# motor_driver_ver3_2.net
KiCad netlist of a schematic drawn in EAGLE
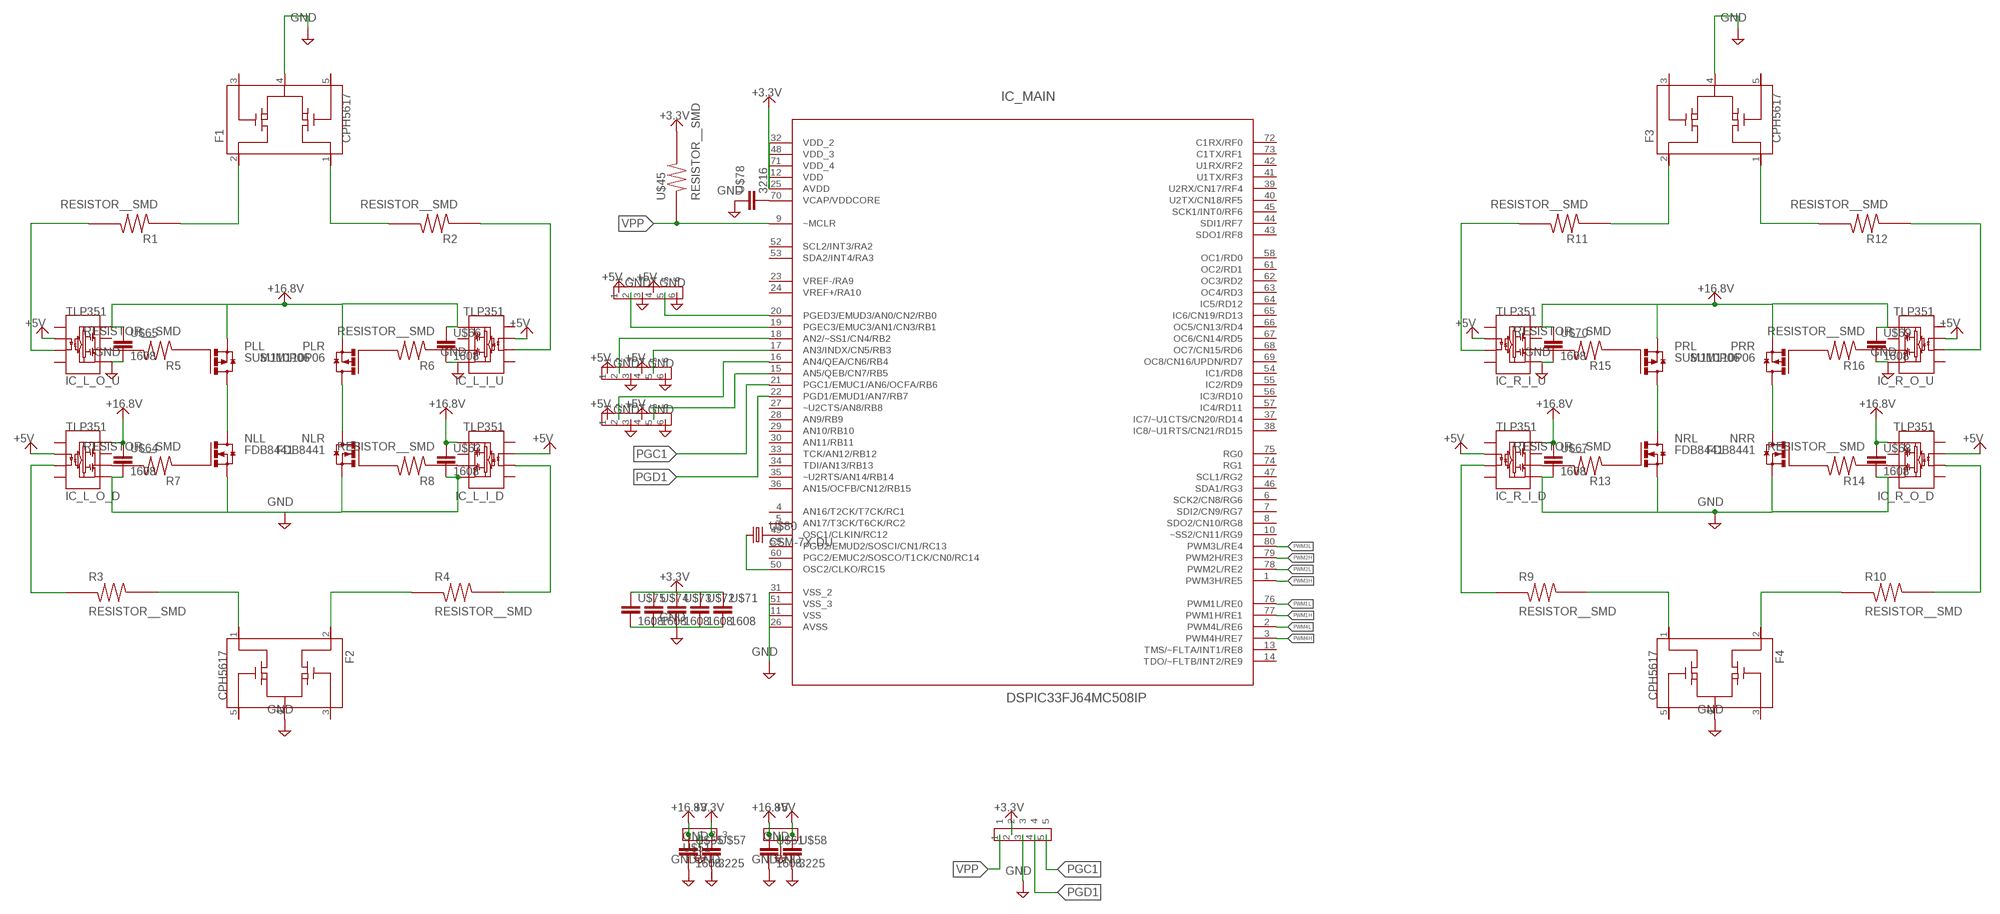
[diagram p0: schematic, sheet 1]

(export (version "E")
  (design (tool "Eeschema 10.0.6"))
  (components
    (comp (ref "F1")
      (value "CPH5617")
      (footprint "eagle-import:CHP-5")
      (libsource (lib "eagle-import") (part "CPH5617"))
    )
    (comp (ref "F2")
      (value "CPH5617")
      (footprint "eagle-import:CHP-5")
      (libsource (lib "eagle-import") (part "CPH5617"))
    )
    (comp (ref "F3")
      (value "CPH5617")
      (footprint "eagle-import:CHP-5")
      (libsource (lib "eagle-import") (part "CPH5617"))
    )
    (comp (ref "F4")
      (value "CPH5617")
      (footprint "eagle-import:CHP-5")
      (libsource (lib "eagle-import") (part "CPH5617"))
    )
    (comp (ref "IC_L_I_D")
      (value "TLP351")
      (footprint "eagle-import:DIL08")
      (libsource (lib "eagle-import") (part "TLP351"))
    )
    (comp (ref "IC_L_I_U")
      (value "TLP351")
      (footprint "eagle-import:DIL08")
      (libsource (lib "eagle-import") (part "TLP351"))
    )
    (comp (ref "IC_L_O_D")
      (value "TLP351")
      (footprint "eagle-import:DIL08")
      (libsource (lib "eagle-import") (part "TLP351"))
    )
    (comp (ref "IC_L_O_U")
      (value "TLP351")
      (footprint "eagle-import:DIL08")
      (libsource (lib "eagle-import") (part "TLP351"))
    )
    (comp (ref "IC_MAIN")
      (value "DSPIC33FJ64MC508IP")
      (footprint "eagle-import:QFP50P1400X1400X120-80N")
      (libsource (lib "eagle-import") (part "DSPIC33FJ64MC508IP"))
    )
    (comp (ref "IC_R_I_D")
      (value "TLP351")
      (footprint "eagle-import:DIL08")
      (libsource (lib "eagle-import") (part "TLP351"))
    )
    (comp (ref "IC_R_I_U")
      (value "TLP351")
      (footprint "eagle-import:DIL08")
      (libsource (lib "eagle-import") (part "TLP351"))
    )
    (comp (ref "IC_R_O_D")
      (value "TLP351")
      (footprint "eagle-import:DIL08")
      (libsource (lib "eagle-import") (part "TLP351"))
    )
    (comp (ref "IC_R_O_U")
      (value "TLP351")
      (footprint "eagle-import:DIL08")
      (libsource (lib "eagle-import") (part "TLP351"))
    )
    (comp (ref "NLL")
      (value "FDB8441")
      (footprint "eagle-import:TO-263")
      (libsource (lib "eagle-import") (part "FDB8441"))
    )
    (comp (ref "NLR")
      (value "FDB8441")
      (footprint "eagle-import:TO-263")
      (libsource (lib "eagle-import") (part "FDB8441"))
    )
    (comp (ref "NRL")
      (value "FDB8441")
      (footprint "eagle-import:TO-263")
      (libsource (lib "eagle-import") (part "FDB8441"))
    )
    (comp (ref "NRR")
      (value "FDB8441")
      (footprint "eagle-import:TO-263")
      (libsource (lib "eagle-import") (part "FDB8441"))
    )
    (comp (ref "PLL")
      (value "SUM110P06")
      (footprint "eagle-import:TO-263")
      (libsource (lib "eagle-import") (part "SUM110P06"))
    )
    (comp (ref "PLR")
      (value "SUM110P06")
      (footprint "eagle-import:TO-263")
      (libsource (lib "eagle-import") (part "SUM110P06"))
    )
    (comp (ref "PRL")
      (value "SUM110P06")
      (footprint "eagle-import:TO-263")
      (libsource (lib "eagle-import") (part "SUM110P06"))
    )
    (comp (ref "PRR")
      (value "SUM110P06")
      (footprint "eagle-import:TO-263")
      (libsource (lib "eagle-import") (part "SUM110P06"))
    )
    (comp (ref "R1")
      (value "RESISTOR__SMD")
      (footprint "eagle-import:1608")
      (libsource (lib "eagle-import") (part "RESISTOR__SMD"))
    )
    (comp (ref "R2")
      (value "RESISTOR__SMD")
      (footprint "eagle-import:1608")
      (libsource (lib "eagle-import") (part "RESISTOR__SMD"))
    )
    (comp (ref "R3")
      (value "RESISTOR__SMD")
      (footprint "eagle-import:1608")
      (libsource (lib "eagle-import") (part "RESISTOR__SMD"))
    )
    (comp (ref "R4")
      (value "RESISTOR__SMD")
      (footprint "eagle-import:1608")
      (libsource (lib "eagle-import") (part "RESISTOR__SMD"))
    )
    (comp (ref "R5")
      (value "RESISTOR__SMD")
      (footprint "eagle-import:1608")
      (libsource (lib "eagle-import") (part "RESISTOR__SMD"))
    )
    (comp (ref "R6")
      (value "RESISTOR__SMD")
      (footprint "eagle-import:1608")
      (libsource (lib "eagle-import") (part "RESISTOR__SMD"))
    )
    (comp (ref "R7")
      (value "RESISTOR__SMD")
      (footprint "eagle-import:1608")
      (libsource (lib "eagle-import") (part "RESISTOR__SMD"))
    )
    (comp (ref "R8")
      (value "RESISTOR__SMD")
      (footprint "eagle-import:1608")
      (libsource (lib "eagle-import") (part "RESISTOR__SMD"))
    )
    (comp (ref "R9")
      (value "RESISTOR__SMD")
      (footprint "eagle-import:1608")
      (libsource (lib "eagle-import") (part "RESISTOR__SMD"))
    )
    (comp (ref "R10")
      (value "RESISTOR__SMD")
      (footprint "eagle-import:1608")
      (libsource (lib "eagle-import") (part "RESISTOR__SMD"))
    )
    (comp (ref "R11")
      (value "RESISTOR__SMD")
      (footprint "eagle-import:1608")
      (libsource (lib "eagle-import") (part "RESISTOR__SMD"))
    )
    (comp (ref "R12")
      (value "RESISTOR__SMD")
      (footprint "eagle-import:1608")
      (libsource (lib "eagle-import") (part "RESISTOR__SMD"))
    )
    (comp (ref "R13")
      (value "RESISTOR__SMD")
      (footprint "eagle-import:1608")
      (libsource (lib "eagle-import") (part "RESISTOR__SMD"))
    )
    (comp (ref "R14")
      (value "RESISTOR__SMD")
      (footprint "eagle-import:1608")
      (libsource (lib "eagle-import") (part "RESISTOR__SMD"))
    )
    (comp (ref "R15")
      (value "RESISTOR__SMD")
      (footprint "eagle-import:1608")
      (libsource (lib "eagle-import") (part "RESISTOR__SMD"))
    )
    (comp (ref "R16")
      (value "RESISTOR__SMD")
      (footprint "eagle-import:1608")
      (libsource (lib "eagle-import") (part "RESISTOR__SMD"))
    )
    (comp (ref "U$1")
      (value "PIN_HEADER_5")
      (footprint "eagle-import:PIN_HEADER_5")
      (libsource (lib "eagle-import") (part "PIN_HEADER_5"))
    )
    (comp (ref "U$4")
      (value "PIN_HEADER_6")
      (footprint "eagle-import:PIN_HEADER_6")
      (libsource (lib "eagle-import") (part "PIN_HEADER_6"))
    )
    (comp (ref "U$5")
      (value "PIN_HEADER_6")
      (footprint "eagle-import:PIN_HEADER_6")
      (libsource (lib "eagle-import") (part "PIN_HEADER_6"))
    )
    (comp (ref "U$20")
      (value "PIN_HEADER_6")
      (footprint "eagle-import:PIN_HEADER_6")
      (libsource (lib "eagle-import") (part "PIN_HEADER_6"))
    )
    (comp (ref "U$45")
      (value "RESISTOR__SMD")
      (footprint "eagle-import:1608")
      (libsource (lib "eagle-import") (part "RESISTOR__SMD"))
    )
    (comp (ref "U$47")
      (value "TA48M05")
      (footprint "eagle-import:ＨＳＩＰ３")
      (libsource (lib "eagle-import") (part "TA48M05"))
    )
    (comp (ref "U$51")
      (value "TA48M033")
      (footprint "eagle-import:ＨＳＩＰ３")
      (libsource (lib "eagle-import") (part "TA48M033"))
    )
    (comp (ref "U$55")
      (value "1608")
      (footprint "eagle-import:1608")
      (libsource (lib "eagle-import") (part "1608"))
    )
    (comp (ref "U$57")
      (value "3225")
      (footprint "eagle-import:3225")
      (libsource (lib "eagle-import") (part "3225"))
    )
    (comp (ref "U$58")
      (value "3225")
      (footprint "eagle-import:3225")
      (libsource (lib "eagle-import") (part "3225"))
    )
    (comp (ref "U$61")
      (value "1608")
      (footprint "eagle-import:1608")
      (libsource (lib "eagle-import") (part "1608"))
    )
    (comp (ref "U$63")
      (value "1608")
      (footprint "eagle-import:1608")
      (libsource (lib "eagle-import") (part "1608"))
    )
    (comp (ref "U$64")
      (value "1608")
      (footprint "eagle-import:1608")
      (libsource (lib "eagle-import") (part "1608"))
    )
    (comp (ref "U$65")
      (value "1608")
      (footprint "eagle-import:1608")
      (libsource (lib "eagle-import") (part "1608"))
    )
    (comp (ref "U$66")
      (value "1608")
      (footprint "eagle-import:1608")
      (libsource (lib "eagle-import") (part "1608"))
    )
    (comp (ref "U$67")
      (value "1608")
      (footprint "eagle-import:1608")
      (libsource (lib "eagle-import") (part "1608"))
    )
    (comp (ref "U$68")
      (value "1608")
      (footprint "eagle-import:1608")
      (libsource (lib "eagle-import") (part "1608"))
    )
    (comp (ref "U$69")
      (value "1608")
      (footprint "eagle-import:1608")
      (libsource (lib "eagle-import") (part "1608"))
    )
    (comp (ref "U$70")
      (value "1608")
      (footprint "eagle-import:1608")
      (libsource (lib "eagle-import") (part "1608"))
    )
    (comp (ref "U$71")
      (value "1608")
      (footprint "eagle-import:1608")
      (libsource (lib "eagle-import") (part "1608"))
    )
    (comp (ref "U$72")
      (value "1608")
      (footprint "eagle-import:1608")
      (libsource (lib "eagle-import") (part "1608"))
    )
    (comp (ref "U$73")
      (value "1608")
      (footprint "eagle-import:1608")
      (libsource (lib "eagle-import") (part "1608"))
    )
    (comp (ref "U$74")
      (value "1608")
      (footprint "eagle-import:1608")
      (libsource (lib "eagle-import") (part "1608"))
    )
    (comp (ref "U$75")
      (value "1608")
      (footprint "eagle-import:1608")
      (libsource (lib "eagle-import") (part "1608"))
    )
    (comp (ref "U$78")
      (value "3216")
      (footprint "eagle-import:3216")
      (libsource (lib "eagle-import") (part "3216"))
    )
    (comp (ref "U$80")
      (value "CSM-7X-DU")
      (footprint "eagle-import:CSM-7X-DU")
      (libsource (lib "eagle-import") (part "CSM-7X-DU"))
    )
  )
  (nets
    (net (code "1") (name "+3.3V") (class "Default")
      (node (ref "IC_MAIN") (pin "12") (pinfunction "VDD_12") (pintype "power_in"))
      (node (ref "IC_MAIN") (pin "25") (pinfunction "AVDD_25") (pintype "power_in"))
      (node (ref "IC_MAIN") (pin "32") (pinfunction "VDD_2_32") (pintype "power_in"))
      (node (ref "IC_MAIN") (pin "48") (pinfunction "VDD_3_48") (pintype "power_in"))
      (node (ref "IC_MAIN") (pin "71") (pinfunction "VDD_4_71") (pintype "power_in"))
      (node (ref "U$1") (pin "2") (pinfunction "2_2") (pintype "bidirectional"))
      (node (ref "U$45") (pin "2") (pinfunction "P$2_2") (pintype "passive"))
      (node (ref "U$51") (pin "3") (pinfunction "3_3") (pintype "bidirectional"))
      (node (ref "U$57") (pin "P$1") (pinfunction "1_P$1") (pintype "passive"))
      (node (ref "U$71") (pin "P$1") (pinfunction "1_P$1") (pintype "passive"))
      (node (ref "U$72") (pin "P$1") (pinfunction "1_P$1") (pintype "passive"))
      (node (ref "U$73") (pin "P$1") (pinfunction "1_P$1") (pintype "passive"))
      (node (ref "U$74") (pin "P$1") (pinfunction "1_P$1") (pintype "passive"))
      (node (ref "U$75") (pin "P$1") (pinfunction "1_P$1") (pintype "passive"))
    )
    (net (code "2") (name "+5V") (class "Default")
      (node (ref "IC_L_I_D") (pin "2") (pinfunction "LED+_2") (pintype "bidirectional"))
      (node (ref "IC_L_I_U") (pin "2") (pinfunction "LED+_2") (pintype "bidirectional"))
      (node (ref "IC_L_O_D") (pin "2") (pinfunction "LED+_2") (pintype "bidirectional"))
      (node (ref "IC_L_O_U") (pin "2") (pinfunction "LED+_2") (pintype "bidirectional"))
      (node (ref "IC_R_I_D") (pin "2") (pinfunction "LED+_2") (pintype "bidirectional"))
      (node (ref "IC_R_I_U") (pin "2") (pinfunction "LED+_2") (pintype "bidirectional"))
      (node (ref "IC_R_O_D") (pin "2") (pinfunction "LED+_2") (pintype "bidirectional"))
      (node (ref "IC_R_O_U") (pin "2") (pinfunction "LED+_2") (pintype "bidirectional"))
      (node (ref "U$20") (pin "1") (pinfunction "1_1") (pintype "bidirectional"))
      (node (ref "U$20") (pin "4") (pinfunction "4_4") (pintype "bidirectional"))
      (node (ref "U$4") (pin "1") (pinfunction "1_1") (pintype "bidirectional"))
      (node (ref "U$4") (pin "4") (pinfunction "4_4") (pintype "bidirectional"))
      (node (ref "U$47") (pin "3") (pinfunction "OUT_3") (pintype "bidirectional"))
      (node (ref "U$5") (pin "1") (pinfunction "1_1") (pintype "bidirectional"))
      (node (ref "U$5") (pin "4") (pinfunction "4_4") (pintype "bidirectional"))
      (node (ref "U$58") (pin "P$1") (pinfunction "1_P$1") (pintype "passive"))
    )
    (net (code "3") (name "+16.8V") (class "Default")
      (node (ref "IC_L_I_D") (pin "8") (pinfunction "VDD_8") (pintype "bidirectional"))
      (node (ref "IC_L_I_U") (pin "8") (pinfunction "VDD_8") (pintype "bidirectional"))
      (node (ref "IC_L_O_D") (pin "8") (pinfunction "VDD_8") (pintype "bidirectional"))
      (node (ref "IC_L_O_U") (pin "8") (pinfunction "VDD_8") (pintype "bidirectional"))
      (node (ref "IC_R_I_D") (pin "8") (pinfunction "VDD_8") (pintype "bidirectional"))
      (node (ref "IC_R_I_U") (pin "8") (pinfunction "VDD_8") (pintype "bidirectional"))
      (node (ref "IC_R_O_D") (pin "8") (pinfunction "VDD_8") (pintype "bidirectional"))
      (node (ref "IC_R_O_U") (pin "8") (pinfunction "VDD_8") (pintype "bidirectional"))
      (node (ref "PLL") (pin "2") (pinfunction "S_2") (pintype "passive"))
      (node (ref "PLR") (pin "2") (pinfunction "S_2") (pintype "passive"))
      (node (ref "PRL") (pin "2") (pinfunction "S_2") (pintype "passive"))
      (node (ref "PRR") (pin "2") (pinfunction "S_2") (pintype "passive"))
      (node (ref "U$47") (pin "1") (pinfunction "IN_1") (pintype "bidirectional"))
      (node (ref "U$51") (pin "1") (pinfunction "1_1") (pintype "bidirectional"))
      (node (ref "U$55") (pin "P$1") (pinfunction "1_P$1") (pintype "passive"))
      (node (ref "U$61") (pin "P$1") (pinfunction "1_P$1") (pintype "passive"))
      (node (ref "U$63") (pin "P$1") (pinfunction "1_P$1") (pintype "passive"))
      (node (ref "U$64") (pin "P$1") (pinfunction "1_P$1") (pintype "passive"))
      (node (ref "U$65") (pin "P$1") (pinfunction "1_P$1") (pintype "passive"))
      (node (ref "U$66") (pin "P$1") (pinfunction "1_P$1") (pintype "passive"))
      (node (ref "U$67") (pin "P$1") (pinfunction "1_P$1") (pintype "passive"))
      (node (ref "U$68") (pin "P$1") (pinfunction "1_P$1") (pintype "passive"))
      (node (ref "U$69") (pin "P$1") (pinfunction "1_P$1") (pintype "passive"))
      (node (ref "U$70") (pin "P$1") (pinfunction "1_P$1") (pintype "passive"))
    )
    (net (code "4") (name "GND") (class "Default")
      (node (ref "F1") (pin "4") (pinfunction "S_4") (pintype "bidirectional"))
      (node (ref "F2") (pin "4") (pinfunction "S_4") (pintype "bidirectional"))
      (node (ref "F3") (pin "4") (pinfunction "S_4") (pintype "bidirectional"))
      (node (ref "F4") (pin "4") (pinfunction "S_4") (pintype "bidirectional"))
      (node (ref "IC_L_I_D") (pin "5") (pinfunction "GND_5") (pintype "bidirectional"))
      (node (ref "IC_L_I_U") (pin "5") (pinfunction "GND_5") (pintype "bidirectional"))
      (node (ref "IC_L_O_D") (pin "5") (pinfunction "GND_5") (pintype "bidirectional"))
      (node (ref "IC_L_O_U") (pin "5") (pinfunction "GND_5") (pintype "bidirectional"))
      (node (ref "IC_MAIN") (pin "11") (pinfunction "VSS_11") (pintype "power_in"))
      (node (ref "IC_MAIN") (pin "26") (pinfunction "AVSS_26") (pintype "power_in"))
      (node (ref "IC_MAIN") (pin "31") (pinfunction "VSS_2_31") (pintype "power_in"))
      (node (ref "IC_MAIN") (pin "51") (pinfunction "VSS_3_51") (pintype "power_in"))
      (node (ref "IC_R_I_D") (pin "5") (pinfunction "GND_5") (pintype "bidirectional"))
      (node (ref "IC_R_I_U") (pin "5") (pinfunction "GND_5") (pintype "bidirectional"))
      (node (ref "IC_R_O_D") (pin "5") (pinfunction "GND_5") (pintype "bidirectional"))
      (node (ref "IC_R_O_U") (pin "5") (pinfunction "GND_5") (pintype "bidirectional"))
      (node (ref "NLL") (pin "2") (pinfunction "S_2") (pintype "passive"))
      (node (ref "NLR") (pin "2") (pinfunction "S_2") (pintype "passive"))
      (node (ref "NRL") (pin "2") (pinfunction "S_2") (pintype "passive"))
      (node (ref "NRR") (pin "2") (pinfunction "S_2") (pintype "passive"))
      (node (ref "U$1") (pin "3") (pinfunction "3_3") (pintype "bidirectional"))
      (node (ref "U$20") (pin "3") (pinfunction "3_3") (pintype "bidirectional"))
      (node (ref "U$20") (pin "6") (pinfunction "6_6") (pintype "bidirectional"))
      (node (ref "U$4") (pin "3") (pinfunction "3_3") (pintype "bidirectional"))
      (node (ref "U$4") (pin "6") (pinfunction "6_6") (pintype "bidirectional"))
      (node (ref "U$47") (pin "2") (pinfunction "GND_2") (pintype "bidirectional"))
      (node (ref "U$5") (pin "3") (pinfunction "3_3") (pintype "bidirectional"))
      (node (ref "U$5") (pin "6") (pinfunction "6_6") (pintype "bidirectional"))
      (node (ref "U$51") (pin "2") (pinfunction "2_2") (pintype "bidirectional"))
      (node (ref "U$55") (pin "P$2") (pinfunction "2_P$2") (pintype "passive"))
      (node (ref "U$57") (pin "P$2") (pinfunction "2_P$2") (pintype "passive"))
      (node (ref "U$58") (pin "P$2") (pinfunction "2_P$2") (pintype "passive"))
      (node (ref "U$61") (pin "P$2") (pinfunction "2_P$2") (pintype "passive"))
      (node (ref "U$63") (pin "P$2") (pinfunction "2_P$2") (pintype "passive"))
      (node (ref "U$64") (pin "P$2") (pinfunction "2_P$2") (pintype "passive"))
      (node (ref "U$65") (pin "P$2") (pinfunction "2_P$2") (pintype "passive"))
      (node (ref "U$66") (pin "P$2") (pinfunction "2_P$2") (pintype "passive"))
      (node (ref "U$67") (pin "P$2") (pinfunction "2_P$2") (pintype "passive"))
      (node (ref "U$68") (pin "P$2") (pinfunction "2_P$2") (pintype "passive"))
      (node (ref "U$69") (pin "P$2") (pinfunction "2_P$2") (pintype "passive"))
      (node (ref "U$70") (pin "P$2") (pinfunction "2_P$2") (pintype "passive"))
      (node (ref "U$71") (pin "P$2") (pinfunction "2_P$2") (pintype "passive"))
      (node (ref "U$72") (pin "P$2") (pinfunction "2_P$2") (pintype "passive"))
      (node (ref "U$73") (pin "P$2") (pinfunction "2_P$2") (pintype "passive"))
      (node (ref "U$74") (pin "P$2") (pinfunction "2_P$2") (pintype "passive"))
      (node (ref "U$75") (pin "P$2") (pinfunction "2_P$2") (pintype "passive"))
      (node (ref "U$78") (pin "P$1") (pinfunction "1_P$1") (pintype "passive"))
    )
    (net (code "5") (name "Net-(F1-D1)") (class "Default")
      (node (ref "F1") (pin "1") (pinfunction "D1_1") (pintype "bidirectional"))
      (node (ref "R2") (pin "2") (pinfunction "P$2_2") (pintype "passive"))
    )
    (net (code "6") (name "Net-(F1-D2)") (class "Default")
      (node (ref "F1") (pin "2") (pinfunction "D2_2") (pintype "bidirectional"))
      (node (ref "R1") (pin "1") (pinfunction "P$1_1") (pintype "passive"))
    )
    (net (code "7") (name "Net-(F2-D1)") (class "Default")
      (node (ref "F2") (pin "1") (pinfunction "D1_1") (pintype "bidirectional"))
      (node (ref "R3") (pin "2") (pinfunction "P$2_2") (pintype "passive"))
    )
    (net (code "8") (name "Net-(F2-D2)") (class "Default")
      (node (ref "F2") (pin "2") (pinfunction "D2_2") (pintype "bidirectional"))
      (node (ref "R4") (pin "1") (pinfunction "P$1_1") (pintype "passive"))
    )
    (net (code "9") (name "Net-(F3-D1)") (class "Default")
      (node (ref "F3") (pin "1") (pinfunction "D1_1") (pintype "bidirectional"))
      (node (ref "R12") (pin "2") (pinfunction "P$2_2") (pintype "passive"))
    )
    (net (code "10") (name "Net-(F3-D2)") (class "Default")
      (node (ref "F3") (pin "2") (pinfunction "D2_2") (pintype "bidirectional"))
      (node (ref "R11") (pin "1") (pinfunction "P$1_1") (pintype "passive"))
    )
    (net (code "11") (name "Net-(F4-D1)") (class "Default")
      (node (ref "F4") (pin "1") (pinfunction "D1_1") (pintype "bidirectional"))
      (node (ref "R9") (pin "2") (pinfunction "P$2_2") (pintype "passive"))
    )
    (net (code "12") (name "Net-(F4-D2)") (class "Default")
      (node (ref "F4") (pin "2") (pinfunction "D2_2") (pintype "bidirectional"))
      (node (ref "R10") (pin "1") (pinfunction "P$1_1") (pintype "passive"))
    )
    (net (code "13") (name "Net-(IC_L_I_D-LED-)") (class "Default")
      (node (ref "IC_L_I_D") (pin "3") (pinfunction "LED-_3") (pintype "bidirectional"))
      (node (ref "R4") (pin "2") (pinfunction "P$2_2") (pintype "passive"))
    )
    (net (code "14") (name "Net-(IC_L_I_D-OUT)") (class "Default")
      (node (ref "IC_L_I_D") (pin "6") (pinfunction "OUT_6") (pintype "output"))
      (node (ref "R8") (pin "1") (pinfunction "P$1_1") (pintype "passive"))
    )
    (net (code "15") (name "Net-(IC_L_I_U-LED-)") (class "Default")
      (node (ref "IC_L_I_U") (pin "3") (pinfunction "LED-_3") (pintype "bidirectional"))
      (node (ref "R2") (pin "1") (pinfunction "P$1_1") (pintype "passive"))
    )
    (net (code "16") (name "Net-(IC_L_I_U-OUT)") (class "Default")
      (node (ref "IC_L_I_U") (pin "6") (pinfunction "OUT_6") (pintype "output"))
      (node (ref "R6") (pin "1") (pinfunction "P$1_1") (pintype "passive"))
    )
    (net (code "17") (name "Net-(IC_L_O_D-LED-)") (class "Default")
      (node (ref "IC_L_O_D") (pin "3") (pinfunction "LED-_3") (pintype "bidirectional"))
      (node (ref "R3") (pin "1") (pinfunction "P$1_1") (pintype "passive"))
    )
    (net (code "18") (name "Net-(IC_L_O_D-OUT)") (class "Default")
      (node (ref "IC_L_O_D") (pin "6") (pinfunction "OUT_6") (pintype "output"))
      (node (ref "R7") (pin "2") (pinfunction "P$2_2") (pintype "passive"))
    )
    (net (code "19") (name "Net-(IC_L_O_U-LED-)") (class "Default")
      (node (ref "IC_L_O_U") (pin "3") (pinfunction "LED-_3") (pintype "bidirectional"))
      (node (ref "R1") (pin "2") (pinfunction "P$2_2") (pintype "passive"))
    )
    (net (code "20") (name "Net-(IC_L_O_U-OUT)") (class "Default")
      (node (ref "IC_L_O_U") (pin "6") (pinfunction "OUT_6") (pintype "output"))
      (node (ref "R5") (pin "2") (pinfunction "P$2_2") (pintype "passive"))
    )
    (net (code "21") (name "Net-(IC_MAIN-AN2{slash}~{SS1{slash}CN4{slash}RB2})") (class "Default")
      (node (ref "IC_MAIN") (pin "18") (pinfunction "AN2/~{SS1/CN4/RB2}_18") (pintype "bidirectional"))
      (node (ref "U$5") (pin "2") (pinfunction "2_2") (pintype "bidirectional"))
    )
    (net (code "22") (name "Net-(IC_MAIN-AN3{slash}INDX{slash}CN5{slash}RB3)") (class "Default")
      (node (ref "IC_MAIN") (pin "17") (pinfunction "AN3/INDX/CN5/RB3_17") (pintype "bidirectional"))
      (node (ref "U$5") (pin "5") (pinfunction "5_5") (pintype "bidirectional"))
    )
    (net (code "23") (name "Net-(IC_MAIN-AN4{slash}QEA{slash}CN6{slash}RB4)") (class "Default")
      (node (ref "IC_MAIN") (pin "16") (pinfunction "AN4/QEA/CN6/RB4_16") (pintype "bidirectional"))
      (node (ref "U$20") (pin "2") (pinfunction "2_2") (pintype "bidirectional"))
    )
    (net (code "24") (name "Net-(IC_MAIN-AN5{slash}QEB{slash}CN7{slash}RB5)") (class "Default")
      (node (ref "IC_MAIN") (pin "15") (pinfunction "AN5/QEB/CN7/RB5_15") (pintype "bidirectional"))
      (node (ref "U$20") (pin "5") (pinfunction "5_5") (pintype "bidirectional"))
    )
    (net (code "25") (name "Net-(IC_MAIN-OSC1{slash}CLKIN{slash}RC12)") (class "Default")
      (node (ref "IC_MAIN") (pin "49") (pinfunction "OSC1/CLKIN/RC12_49") (pintype "bidirectional"))
      (node (ref "U$80") (pin "2") (pinfunction "2_2") (pintype "passive"))
    )
    (net (code "26") (name "Net-(IC_MAIN-OSC2{slash}CLKO{slash}RC15)") (class "Default")
      (node (ref "IC_MAIN") (pin "50") (pinfunction "OSC2/CLKO/RC15_50") (pintype "bidirectional"))
      (node (ref "U$80") (pin "1") (pinfunction "1_1") (pintype "passive"))
    )
    (net (code "27") (name "Net-(IC_MAIN-PGEC3{slash}EMUC3{slash}AN1{slash}CN3{slash}RB1)") (class "Default")
      (node (ref "IC_MAIN") (pin "19") (pinfunction "PGEC3/EMUC3/AN1/CN3/RB1_19") (pintype "bidirectional"))
      (node (ref "U$4") (pin "2") (pinfunction "2_2") (pintype "bidirectional"))
    )
    (net (code "28") (name "Net-(IC_MAIN-PGED3{slash}EMUD3{slash}AN0{slash}CN2{slash}RB0)") (class "Default")
      (node (ref "IC_MAIN") (pin "20") (pinfunction "PGED3/EMUD3/AN0/CN2/RB0_20") (pintype "bidirectional"))
      (node (ref "U$4") (pin "5") (pinfunction "5_5") (pintype "bidirectional"))
    )
    (net (code "29") (name "Net-(IC_MAIN-VCAP{slash}VDDCORE)") (class "Default")
      (node (ref "IC_MAIN") (pin "70") (pinfunction "VCAP/VDDCORE_70") (pintype "power_in"))
      (node (ref "U$78") (pin "P$2") (pinfunction "2_P$2") (pintype "passive"))
    )
    (net (code "30") (name "Net-(IC_R_I_D-LED-)") (class "Default")
      (node (ref "IC_R_I_D") (pin "3") (pinfunction "LED-_3") (pintype "bidirectional"))
      (node (ref "R9") (pin "1") (pinfunction "P$1_1") (pintype "passive"))
    )
    (net (code "31") (name "Net-(IC_R_I_D-OUT)") (class "Default")
      (node (ref "IC_R_I_D") (pin "6") (pinfunction "OUT_6") (pintype "output"))
      (node (ref "R13") (pin "2") (pinfunction "P$2_2") (pintype "passive"))
    )
    (net (code "32") (name "Net-(IC_R_I_U-LED-)") (class "Default")
      (node (ref "IC_R_I_U") (pin "3") (pinfunction "LED-_3") (pintype "bidirectional"))
      (node (ref "R11") (pin "2") (pinfunction "P$2_2") (pintype "passive"))
    )
    (net (code "33") (name "Net-(IC_R_I_U-OUT)") (class "Default")
      (node (ref "IC_R_I_U") (pin "6") (pinfunction "OUT_6") (pintype "output"))
      (node (ref "R15") (pin "2") (pinfunction "P$2_2") (pintype "passive"))
    )
    (net (code "34") (name "Net-(IC_R_O_D-LED-)") (class "Default")
      (node (ref "IC_R_O_D") (pin "3") (pinfunction "LED-_3") (pintype "bidirectional"))
      (node (ref "R10") (pin "2") (pinfunction "P$2_2") (pintype "passive"))
    )
    (net (code "35") (name "Net-(IC_R_O_D-OUT)") (class "Default")
      (node (ref "IC_R_O_D") (pin "6") (pinfunction "OUT_6") (pintype "output"))
      (node (ref "R14") (pin "1") (pinfunction "P$1_1") (pintype "passive"))
    )
    (net (code "36") (name "Net-(IC_R_O_U-LED-)") (class "Default")
      (node (ref "IC_R_O_U") (pin "3") (pinfunction "LED-_3") (pintype "bidirectional"))
      (node (ref "R12") (pin "1") (pinfunction "P$1_1") (pintype "passive"))
    )
    (net (code "37") (name "Net-(IC_R_O_U-OUT)") (class "Default")
      (node (ref "IC_R_O_U") (pin "6") (pinfunction "OUT_6") (pintype "output"))
      (node (ref "R16") (pin "1") (pinfunction "P$1_1") (pintype "passive"))
    )
    (net (code "38") (name "Net-(NLL-D)") (class "Default")
      (node (ref "NLL") (pin "3") (pinfunction "D_3") (pintype "passive"))
      (node (ref "PLL") (pin "3") (pinfunction "D_3") (pintype "passive"))
    )
    (net (code "39") (name "Net-(NLL-G)") (class "Default")
      (node (ref "NLL") (pin "1") (pinfunction "G_1") (pintype "passive"))
      (node (ref "R7") (pin "1") (pinfunction "P$1_1") (pintype "passive"))
    )
    (net (code "40") (name "Net-(NLR-D)") (class "Default")
      (node (ref "NLR") (pin "3") (pinfunction "D_3") (pintype "passive"))
      (node (ref "PLR") (pin "3") (pinfunction "D_3") (pintype "passive"))
    )
    (net (code "41") (name "Net-(NLR-G)") (class "Default")
      (node (ref "NLR") (pin "1") (pinfunction "G_1") (pintype "passive"))
      (node (ref "R8") (pin "2") (pinfunction "P$2_2") (pintype "passive"))
    )
    (net (code "42") (name "Net-(NRL-D)") (class "Default")
      (node (ref "NRL") (pin "3") (pinfunction "D_3") (pintype "passive"))
      (node (ref "PRL") (pin "3") (pinfunction "D_3") (pintype "passive"))
    )
    (net (code "43") (name "Net-(NRL-G)") (class "Default")
      (node (ref "NRL") (pin "1") (pinfunction "G_1") (pintype "passive"))
      (node (ref "R13") (pin "1") (pinfunction "P$1_1") (pintype "passive"))
    )
    (net (code "44") (name "Net-(NRR-D)") (class "Default")
      (node (ref "NRR") (pin "3") (pinfunction "D_3") (pintype "passive"))
      (node (ref "PRR") (pin "3") (pinfunction "D_3") (pintype "passive"))
    )
    (net (code "45") (name "Net-(NRR-G)") (class "Default")
      (node (ref "NRR") (pin "1") (pinfunction "G_1") (pintype "passive"))
      (node (ref "R14") (pin "2") (pinfunction "P$2_2") (pintype "passive"))
    )
    (net (code "46") (name "Net-(PLL-G)") (class "Default")
      (node (ref "PLL") (pin "1") (pinfunction "G_1") (pintype "passive"))
      (node (ref "R5") (pin "1") (pinfunction "P$1_1") (pintype "passive"))
    )
    (net (code "47") (name "Net-(PLR-G)") (class "Default")
      (node (ref "PLR") (pin "1") (pinfunction "G_1") (pintype "passive"))
      (node (ref "R6") (pin "2") (pinfunction "P$2_2") (pintype "passive"))
    )
    (net (code "48") (name "Net-(PRL-G)") (class "Default")
      (node (ref "PRL") (pin "1") (pinfunction "G_1") (pintype "passive"))
      (node (ref "R15") (pin "1") (pinfunction "P$1_1") (pintype "passive"))
    )
    (net (code "49") (name "Net-(PRR-G)") (class "Default")
      (node (ref "PRR") (pin "1") (pinfunction "G_1") (pintype "passive"))
      (node (ref "R16") (pin "2") (pinfunction "P$2_2") (pintype "passive"))
    )
    (net (code "50") (name "PGC1") (class "Default")
      (node (ref "IC_MAIN") (pin "21") (pinfunction "PGC1/EMUC1/AN6/OCFA/RB6_21") (pintype "bidirectional"))
      (node (ref "U$1") (pin "5") (pinfunction "5_5") (pintype "bidirectional"))
    )
    (net (code "51") (name "PGD1") (class "Default")
      (node (ref "IC_MAIN") (pin "22") (pinfunction "PGD1/EMUD1/AN7/RB7_22") (pintype "bidirectional"))
      (node (ref "U$1") (pin "4") (pinfunction "4_4") (pintype "bidirectional"))
    )
    (net (code "52") (name "PWM1H") (class "Default")
      (node (ref "IC_MAIN") (pin "77") (pinfunction "PWM1H/RE1_77") (pintype "bidirectional"))
    )
    (net (code "53") (name "PWM1L") (class "Default")
      (node (ref "IC_MAIN") (pin "76") (pinfunction "PWM1L/RE0_76") (pintype "bidirectional"))
    )
    (net (code "54") (name "PWM2H") (class "Default")
      (node (ref "IC_MAIN") (pin "79") (pinfunction "PWM2H/RE3_79") (pintype "bidirectional"))
    )
    (net (code "55") (name "PWM2L") (class "Default")
      (node (ref "IC_MAIN") (pin "78") (pinfunction "PWM2L/RE2_78") (pintype "bidirectional"))
    )
    (net (code "56") (name "PWM3H") (class "Default")
      (node (ref "IC_MAIN") (pin "1") (pinfunction "PWM3H/RE5_1") (pintype "bidirectional"))
    )
    (net (code "57") (name "PWM3L") (class "Default")
      (node (ref "IC_MAIN") (pin "80") (pinfunction "PWM3L/RE4_80") (pintype "bidirectional"))
    )
    (net (code "58") (name "PWM4H") (class "Default")
      (node (ref "IC_MAIN") (pin "3") (pinfunction "PWM4H/RE7_3") (pintype "bidirectional"))
    )
    (net (code "59") (name "PWM4L") (class "Default")
      (node (ref "IC_MAIN") (pin "2") (pinfunction "PWM4L/RE6_2") (pintype "bidirectional"))
    )
    (net (code "60") (name "VPP") (class "Default")
      (node (ref "IC_MAIN") (pin "9") (pinfunction "~{MCLR}_9") (pintype "input"))
      (node (ref "U$1") (pin "1") (pinfunction "1_1") (pintype "bidirectional"))
      (node (ref "U$45") (pin "1") (pinfunction "P$1_1") (pintype "passive"))
    )
    (net (code "61") (name "unconnected-(F1-G1-Pad5)") (class "Default")
      (node (ref "F1") (pin "5") (pinfunction "G1_5") (pintype "bidirectional"))
    )
    (net (code "62") (name "unconnected-(F1-G2-Pad3)") (class "Default")
      (node (ref "F1") (pin "3") (pinfunction "G2_3") (pintype "bidirectional"))
    )
    (net (code "63") (name "unconnected-(F2-G1-Pad5)") (class "Default")
      (node (ref "F2") (pin "5") (pinfunction "G1_5") (pintype "bidirectional"))
    )
    (net (code "64") (name "unconnected-(F2-G2-Pad3)") (class "Default")
      (node (ref "F2") (pin "3") (pinfunction "G2_3") (pintype "bidirectional"))
    )
    (net (code "65") (name "unconnected-(F3-G1-Pad5)") (class "Default")
      (node (ref "F3") (pin "5") (pinfunction "G1_5") (pintype "bidirectional"))
    )
    (net (code "66") (name "unconnected-(F3-G2-Pad3)") (class "Default")
      (node (ref "F3") (pin "3") (pinfunction "G2_3") (pintype "bidirectional"))
    )
    (net (code "67") (name "unconnected-(F4-G1-Pad5)") (class "Default")
      (node (ref "F4") (pin "5") (pinfunction "G1_5") (pintype "bidirectional"))
    )
    (net (code "68") (name "unconnected-(F4-G2-Pad3)") (class "Default")
      (node (ref "F4") (pin "3") (pinfunction "G2_3") (pintype "bidirectional"))
    )
    (net (code "69") (name "unconnected-(IC_L_I_D-NC1-Pad1)") (class "Default")
      (node (ref "IC_L_I_D") (pin "1") (pinfunction "NC1_1") (pintype "no_connect"))
    )
    (net (code "70") (name "unconnected-(IC_L_I_D-NC4-Pad4)") (class "Default")
      (node (ref "IC_L_I_D") (pin "4") (pinfunction "NC4_4") (pintype "no_connect"))
    )
    (net (code "71") (name "unconnected-(IC_L_I_D-NC7-Pad7)") (class "Default")
      (node (ref "IC_L_I_D") (pin "7") (pinfunction "NC7_7") (pintype "no_connect"))
    )
    (net (code "72") (name "unconnected-(IC_L_I_U-NC1-Pad1)") (class "Default")
      (node (ref "IC_L_I_U") (pin "1") (pinfunction "NC1_1") (pintype "no_connect"))
    )
    (net (code "73") (name "unconnected-(IC_L_I_U-NC4-Pad4)") (class "Default")
      (node (ref "IC_L_I_U") (pin "4") (pinfunction "NC4_4") (pintype "no_connect"))
    )
    (net (code "74") (name "unconnected-(IC_L_I_U-NC7-Pad7)") (class "Default")
      (node (ref "IC_L_I_U") (pin "7") (pinfunction "NC7_7") (pintype "no_connect"))
    )
    (net (code "75") (name "unconnected-(IC_L_O_D-NC1-Pad1)") (class "Default")
      (node (ref "IC_L_O_D") (pin "1") (pinfunction "NC1_1") (pintype "no_connect"))
    )
    (net (code "76") (name "unconnected-(IC_L_O_D-NC4-Pad4)") (class "Default")
      (node (ref "IC_L_O_D") (pin "4") (pinfunction "NC4_4") (pintype "no_connect"))
    )
    (net (code "77") (name "unconnected-(IC_L_O_D-NC7-Pad7)") (class "Default")
      (node (ref "IC_L_O_D") (pin "7") (pinfunction "NC7_7") (pintype "no_connect"))
    )
    (net (code "78") (name "unconnected-(IC_L_O_U-NC1-Pad1)") (class "Default")
      (node (ref "IC_L_O_U") (pin "1") (pinfunction "NC1_1") (pintype "no_connect"))
    )
    (net (code "79") (name "unconnected-(IC_L_O_U-NC4-Pad4)") (class "Default")
      (node (ref "IC_L_O_U") (pin "4") (pinfunction "NC4_4") (pintype "no_connect"))
    )
    (net (code "80") (name "unconnected-(IC_L_O_U-NC7-Pad7)") (class "Default")
      (node (ref "IC_L_O_U") (pin "7") (pinfunction "NC7_7") (pintype "no_connect"))
    )
    (net (code "81") (name "unconnected-(IC_MAIN-AN9{slash}RB9-Pad28)") (class "Default")
      (node (ref "IC_MAIN") (pin "28") (pinfunction "AN9/RB9_28") (pintype "bidirectional"))
    )
    (net (code "82") (name "unconnected-(IC_MAIN-AN10{slash}RB10-Pad29)") (class "Default")
      (node (ref "IC_MAIN") (pin "29") (pinfunction "AN10/RB10_29") (pintype "bidirectional"))
    )
    (net (code "83") (name "unconnected-(IC_MAIN-AN11{slash}RB11-Pad30)") (class "Default")
      (node (ref "IC_MAIN") (pin "30") (pinfunction "AN11/RB11_30") (pintype "bidirectional"))
    )
    (net (code "84") (name "unconnected-(IC_MAIN-AN15{slash}OCFB{slash}CN12{slash}RB15-Pad36)") (class "Default")
      (node (ref "IC_MAIN") (pin "36") (pinfunction "AN15/OCFB/CN12/RB15_36") (pintype "bidirectional"))
    )
    (net (code "85") (name "unconnected-(IC_MAIN-AN16{slash}T2CK{slash}T7CK{slash}RC1-Pad4)") (class "Default")
      (node (ref "IC_MAIN") (pin "4") (pinfunction "AN16/T2CK/T7CK/RC1_4") (pintype "bidirectional"))
    )
    (net (code "86") (name "unconnected-(IC_MAIN-AN17{slash}T3CK{slash}T6CK{slash}RC2-Pad5)") (class "Default")
      (node (ref "IC_MAIN") (pin "5") (pinfunction "AN17/T3CK/T6CK/RC2_5") (pintype "bidirectional"))
    )
    (net (code "87") (name "unconnected-(IC_MAIN-C1RX{slash}RF0-Pad72)") (class "Default")
      (node (ref "IC_MAIN") (pin "72") (pinfunction "C1RX/RF0_72") (pintype "bidirectional"))
    )
    (net (code "88") (name "unconnected-(IC_MAIN-C1TX{slash}RF1-Pad73)") (class "Default")
      (node (ref "IC_MAIN") (pin "73") (pinfunction "C1TX/RF1_73") (pintype "bidirectional"))
    )
    (net (code "89") (name "unconnected-(IC_MAIN-IC1{slash}RD8-Pad54)") (class "Default")
      (node (ref "IC_MAIN") (pin "54") (pinfunction "IC1/RD8_54") (pintype "bidirectional"))
    )
    (net (code "90") (name "unconnected-(IC_MAIN-IC2{slash}RD9-Pad55)") (class "Default")
      (node (ref "IC_MAIN") (pin "55") (pinfunction "IC2/RD9_55") (pintype "bidirectional"))
    )
    (net (code "91") (name "unconnected-(IC_MAIN-IC3{slash}RD10-Pad56)") (class "Default")
      (node (ref "IC_MAIN") (pin "56") (pinfunction "IC3/RD10_56") (pintype "bidirectional"))
    )
    (net (code "92") (name "unconnected-(IC_MAIN-IC4{slash}RD11-Pad57)") (class "Default")
      (node (ref "IC_MAIN") (pin "57") (pinfunction "IC4/RD11_57") (pintype "bidirectional"))
    )
    (net (code "93") (name "unconnected-(IC_MAIN-IC5{slash}RD12-Pad64)") (class "Default")
      (node (ref "IC_MAIN") (pin "64") (pinfunction "IC5/RD12_64") (pintype "bidirectional"))
    )
    (net (code "94") (name "unconnected-(IC_MAIN-IC6{slash}CN19{slash}RD13-Pad65)") (class "Default")
      (node (ref "IC_MAIN") (pin "65") (pinfunction "IC6/CN19/RD13_65") (pintype "bidirectional"))
    )
    (net (code "95") (name "unconnected-(IC_MAIN-IC7{slash}~{U1CTS{slash}CN20{slash}RD14}-Pad37)") (class "Default")
      (node (ref "IC_MAIN") (pin "37") (pinfunction "IC7/~{U1CTS/CN20/RD14}_37") (pintype "bidirectional"))
    )
    (net (code "96") (name "unconnected-(IC_MAIN-IC8{slash}~{U1RTS{slash}CN21{slash}RD15}-Pad38)") (class "Default")
      (node (ref "IC_MAIN") (pin "38") (pinfunction "IC8/~{U1RTS/CN21/RD15}_38") (pintype "bidirectional"))
    )
    (net (code "97") (name "unconnected-(IC_MAIN-OC1{slash}RD0-Pad58)") (class "Default")
      (node (ref "IC_MAIN") (pin "58") (pinfunction "OC1/RD0_58") (pintype "bidirectional"))
    )
    (net (code "98") (name "unconnected-(IC_MAIN-OC2{slash}RD1-Pad61)") (class "Default")
      (node (ref "IC_MAIN") (pin "61") (pinfunction "OC2/RD1_61") (pintype "bidirectional"))
    )
    (net (code "99") (name "unconnected-(IC_MAIN-OC3{slash}RD2-Pad62)") (class "Default")
      (node (ref "IC_MAIN") (pin "62") (pinfunction "OC3/RD2_62") (pintype "bidirectional"))
    )
    (net (code "100") (name "unconnected-(IC_MAIN-OC4{slash}RD3-Pad63)") (class "Default")
      (node (ref "IC_MAIN") (pin "63") (pinfunction "OC4/RD3_63") (pintype "bidirectional"))
    )
    (net (code "101") (name "unconnected-(IC_MAIN-OC5{slash}CN13{slash}RD4-Pad66)") (class "Default")
      (node (ref "IC_MAIN") (pin "66") (pinfunction "OC5/CN13/RD4_66") (pintype "bidirectional"))
    )
    (net (code "102") (name "unconnected-(IC_MAIN-OC6{slash}CN14{slash}RD5-Pad67)") (class "Default")
      (node (ref "IC_MAIN") (pin "67") (pinfunction "OC6/CN14/RD5_67") (pintype "bidirectional"))
    )
    (net (code "103") (name "unconnected-(IC_MAIN-OC7{slash}CN15{slash}RD6-Pad68)") (class "Default")
      (node (ref "IC_MAIN") (pin "68") (pinfunction "OC7/CN15/RD6_68") (pintype "bidirectional"))
    )
    (net (code "104") (name "unconnected-(IC_MAIN-OC8{slash}CN16{slash}UPDN{slash}RD7-Pad69)") (class "Default")
      (node (ref "IC_MAIN") (pin "69") (pinfunction "OC8/CN16/UPDN/RD7_69") (pintype "bidirectional"))
    )
    (net (code "105") (name "unconnected-(IC_MAIN-PGC2{slash}EMUC2{slash}SOSCO{slash}T1CK{slash}CN0{slash}RC14-Pad60)") (class "Default")
      (node (ref "IC_MAIN") (pin "60") (pinfunction "PGC2/EMUC2/SOSCO/T1CK/CN0/RC14_60") (pintype "bidirectional"))
    )
    (net (code "106") (name "unconnected-(IC_MAIN-PGD2{slash}EMUD2{slash}SOSCI{slash}CN1{slash}RC13-Pad59)") (class "Default")
      (node (ref "IC_MAIN") (pin "59") (pinfunction "PGD2/EMUD2/SOSCI/CN1/RC13_59") (pintype "bidirectional"))
    )
    (net (code "107") (name "unconnected-(IC_MAIN-RG0-Pad75)") (class "Default")
      (node (ref "IC_MAIN") (pin "75") (pinfunction "RG0_75") (pintype "bidirectional"))
    )
    (net (code "108") (name "unconnected-(IC_MAIN-RG1-Pad74)") (class "Default")
      (node (ref "IC_MAIN") (pin "74") (pinfunction "RG1_74") (pintype "bidirectional"))
    )
    (net (code "109") (name "unconnected-(IC_MAIN-SCK1{slash}INT0{slash}RF6-Pad45)") (class "Default")
      (node (ref "IC_MAIN") (pin "45") (pinfunction "SCK1/INT0/RF6_45") (pintype "bidirectional"))
    )
    (net (code "110") (name "unconnected-(IC_MAIN-SCK2{slash}CN8{slash}RG6-Pad6)") (class "Default")
      (node (ref "IC_MAIN") (pin "6") (pinfunction "SCK2/CN8/RG6_6") (pintype "bidirectional"))
    )
    (net (code "111") (name "unconnected-(IC_MAIN-SCL1{slash}RG2-Pad47)") (class "Default")
      (node (ref "IC_MAIN") (pin "47") (pinfunction "SCL1/RG2_47") (pintype "bidirectional"))
    )
    (net (code "112") (name "unconnected-(IC_MAIN-SCL2{slash}INT3{slash}RA2-Pad52)") (class "Default")
      (node (ref "IC_MAIN") (pin "52") (pinfunction "SCL2/INT3/RA2_52") (pintype "bidirectional"))
    )
    (net (code "113") (name "unconnected-(IC_MAIN-SDA1{slash}RG3-Pad46)") (class "Default")
      (node (ref "IC_MAIN") (pin "46") (pinfunction "SDA1/RG3_46") (pintype "bidirectional"))
    )
    (net (code "114") (name "unconnected-(IC_MAIN-SDA2{slash}INT4{slash}RA3-Pad53)") (class "Default")
      (node (ref "IC_MAIN") (pin "53") (pinfunction "SDA2/INT4/RA3_53") (pintype "bidirectional"))
    )
    (net (code "115") (name "unconnected-(IC_MAIN-SDI1{slash}RF7-Pad44)") (class "Default")
      (node (ref "IC_MAIN") (pin "44") (pinfunction "SDI1/RF7_44") (pintype "bidirectional"))
    )
    (net (code "116") (name "unconnected-(IC_MAIN-SDI2{slash}CN9{slash}RG7-Pad7)") (class "Default")
      (node (ref "IC_MAIN") (pin "7") (pinfunction "SDI2/CN9/RG7_7") (pintype "bidirectional"))
    )
    (net (code "117") (name "unconnected-(IC_MAIN-SDO1{slash}RF8-Pad43)") (class "Default")
      (node (ref "IC_MAIN") (pin "43") (pinfunction "SDO1/RF8_43") (pintype "bidirectional"))
    )
    (net (code "118") (name "unconnected-(IC_MAIN-SDO2{slash}CN10{slash}RG8-Pad8)") (class "Default")
      (node (ref "IC_MAIN") (pin "8") (pinfunction "SDO2/CN10/RG8_8") (pintype "bidirectional"))
    )
    (net (code "119") (name "unconnected-(IC_MAIN-TCK{slash}AN12{slash}RB12-Pad33)") (class "Default")
      (node (ref "IC_MAIN") (pin "33") (pinfunction "TCK/AN12/RB12_33") (pintype "bidirectional"))
    )
    (net (code "120") (name "unconnected-(IC_MAIN-TDI{slash}AN13{slash}RB13-Pad34)") (class "Default")
      (node (ref "IC_MAIN") (pin "34") (pinfunction "TDI/AN13/RB13_34") (pintype "bidirectional"))
    )
    (net (code "121") (name "unconnected-(IC_MAIN-TDO{slash}~{FLTB{slash}INT2{slash}RE9}-Pad14)") (class "Default")
      (node (ref "IC_MAIN") (pin "14") (pinfunction "TDO/~{FLTB/INT2/RE9}_14") (pintype "bidirectional"))
    )
    (net (code "122") (name "unconnected-(IC_MAIN-TMS{slash}~{FLTA{slash}INT1{slash}RE8}-Pad13)") (class "Default")
      (node (ref "IC_MAIN") (pin "13") (pinfunction "TMS/~{FLTA/INT1/RE8}_13") (pintype "bidirectional"))
    )
    (net (code "123") (name "unconnected-(IC_MAIN-U1RX{slash}RF2-Pad42)") (class "Default")
      (node (ref "IC_MAIN") (pin "42") (pinfunction "U1RX/RF2_42") (pintype "bidirectional"))
    )
    (net (code "124") (name "unconnected-(IC_MAIN-U1TX{slash}RF3-Pad41)") (class "Default")
      (node (ref "IC_MAIN") (pin "41") (pinfunction "U1TX/RF3_41") (pintype "bidirectional"))
    )
    (net (code "125") (name "unconnected-(IC_MAIN-U2RX{slash}CN17{slash}RF4-Pad39)") (class "Default")
      (node (ref "IC_MAIN") (pin "39") (pinfunction "U2RX/CN17/RF4_39") (pintype "bidirectional"))
    )
    (net (code "126") (name "unconnected-(IC_MAIN-U2TX{slash}CN18{slash}RF5-Pad40)") (class "Default")
      (node (ref "IC_MAIN") (pin "40") (pinfunction "U2TX/CN18/RF5_40") (pintype "bidirectional"))
    )
    (net (code "127") (name "unconnected-(IC_MAIN-VREF+{slash}RA10-Pad24)") (class "Default")
      (node (ref "IC_MAIN") (pin "24") (pinfunction "VREF+/RA10_24") (pintype "bidirectional"))
    )
    (net (code "128") (name "unconnected-(IC_MAIN-VREF-{slash}RA9-Pad23)") (class "Default")
      (node (ref "IC_MAIN") (pin "23") (pinfunction "VREF-/RA9_23") (pintype "bidirectional"))
    )
    (net (code "129") (name "unconnected-(IC_MAIN-~{SS2{slash}CN11{slash}RG9}-Pad10)") (class "Default")
      (node (ref "IC_MAIN") (pin "10") (pinfunction "~{SS2/CN11/RG9}_10") (pintype "bidirectional"))
    )
    (net (code "130") (name "unconnected-(IC_MAIN-~{U2CTS{slash}AN8{slash}RB8}-Pad27)") (class "Default")
      (node (ref "IC_MAIN") (pin "27") (pinfunction "~{U2CTS/AN8/RB8}_27") (pintype "bidirectional"))
    )
    (net (code "131") (name "unconnected-(IC_MAIN-~{U2RTS{slash}AN14{slash}RB14}-Pad35)") (class "Default")
      (node (ref "IC_MAIN") (pin "35") (pinfunction "~{U2RTS/AN14/RB14}_35") (pintype "bidirectional"))
    )
    (net (code "132") (name "unconnected-(IC_R_I_D-NC1-Pad1)") (class "Default")
      (node (ref "IC_R_I_D") (pin "1") (pinfunction "NC1_1") (pintype "no_connect"))
    )
    (net (code "133") (name "unconnected-(IC_R_I_D-NC4-Pad4)") (class "Default")
      (node (ref "IC_R_I_D") (pin "4") (pinfunction "NC4_4") (pintype "no_connect"))
    )
    (net (code "134") (name "unconnected-(IC_R_I_D-NC7-Pad7)") (class "Default")
      (node (ref "IC_R_I_D") (pin "7") (pinfunction "NC7_7") (pintype "no_connect"))
    )
    (net (code "135") (name "unconnected-(IC_R_I_U-NC1-Pad1)") (class "Default")
      (node (ref "IC_R_I_U") (pin "1") (pinfunction "NC1_1") (pintype "no_connect"))
    )
    (net (code "136") (name "unconnected-(IC_R_I_U-NC4-Pad4)") (class "Default")
      (node (ref "IC_R_I_U") (pin "4") (pinfunction "NC4_4") (pintype "no_connect"))
    )
    (net (code "137") (name "unconnected-(IC_R_I_U-NC7-Pad7)") (class "Default")
      (node (ref "IC_R_I_U") (pin "7") (pinfunction "NC7_7") (pintype "no_connect"))
    )
    (net (code "138") (name "unconnected-(IC_R_O_D-NC1-Pad1)") (class "Default")
      (node (ref "IC_R_O_D") (pin "1") (pinfunction "NC1_1") (pintype "no_connect"))
    )
    (net (code "139") (name "unconnected-(IC_R_O_D-NC4-Pad4)") (class "Default")
      (node (ref "IC_R_O_D") (pin "4") (pinfunction "NC4_4") (pintype "no_connect"))
    )
    (net (code "140") (name "unconnected-(IC_R_O_D-NC7-Pad7)") (class "Default")
      (node (ref "IC_R_O_D") (pin "7") (pinfunction "NC7_7") (pintype "no_connect"))
    )
    (net (code "141") (name "unconnected-(IC_R_O_U-NC1-Pad1)") (class "Default")
      (node (ref "IC_R_O_U") (pin "1") (pinfunction "NC1_1") (pintype "no_connect"))
    )
    (net (code "142") (name "unconnected-(IC_R_O_U-NC4-Pad4)") (class "Default")
      (node (ref "IC_R_O_U") (pin "4") (pinfunction "NC4_4") (pintype "no_connect"))
    )
    (net (code "143") (name "unconnected-(IC_R_O_U-NC7-Pad7)") (class "Default")
      (node (ref "IC_R_O_U") (pin "7") (pinfunction "NC7_7") (pintype "no_connect"))
    )
  )
)
